# FPGA_PWR.net
KiCad netlist of a schematic drawn in Altium Designer
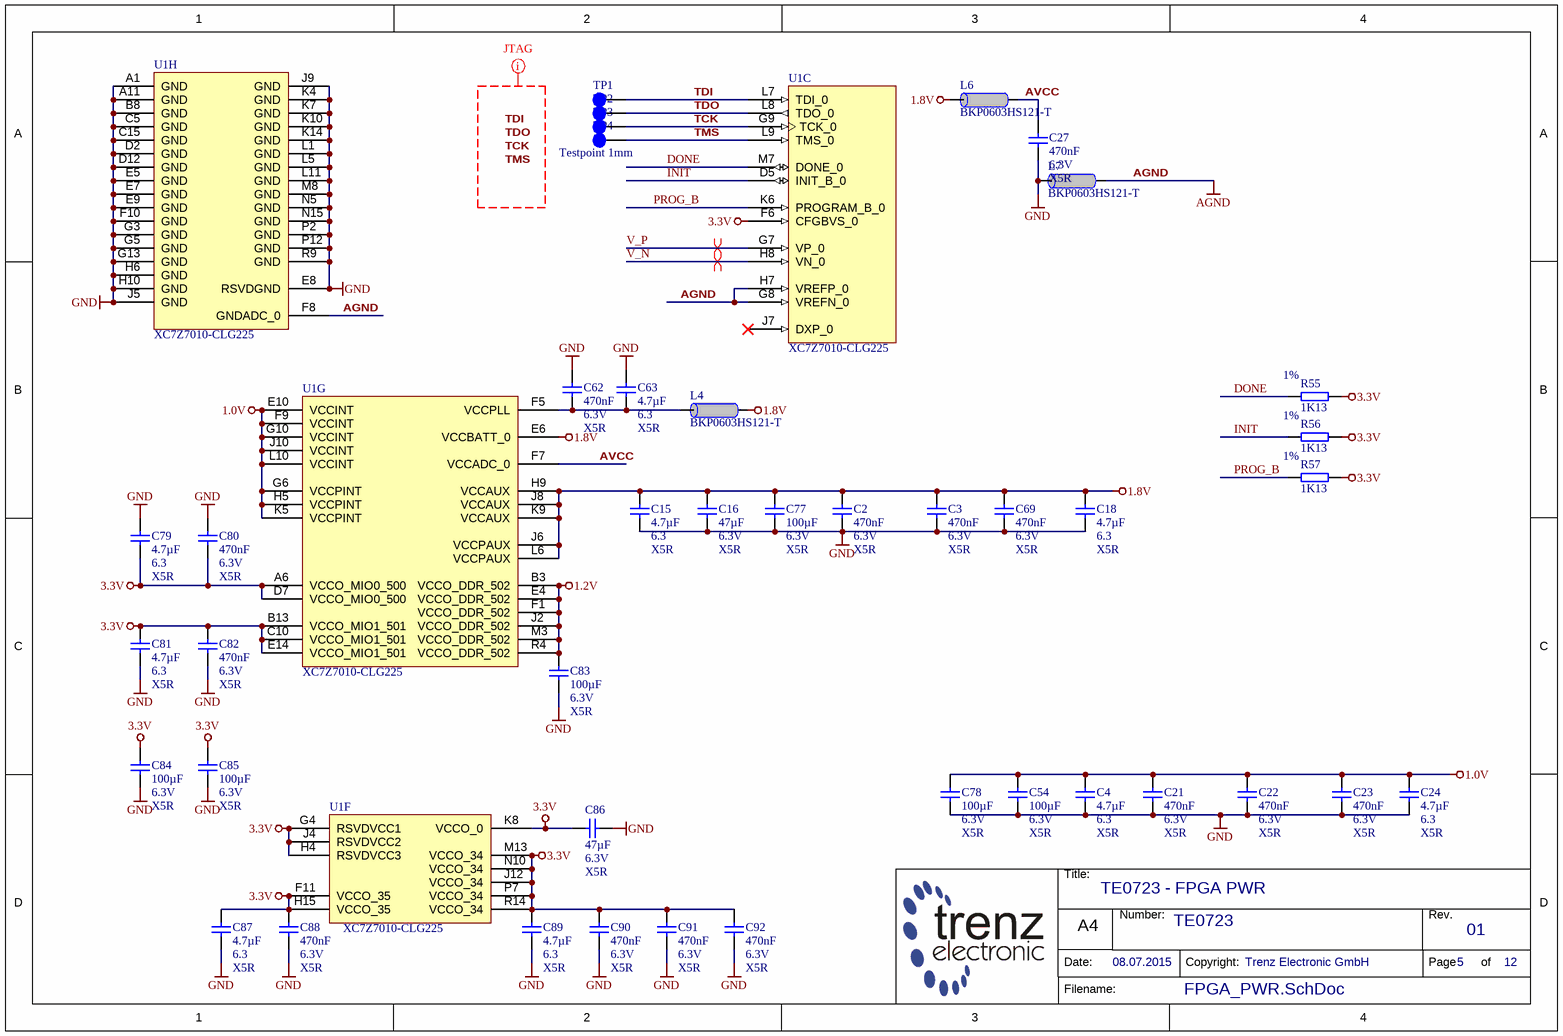
[diagram p0: FPGA_PWR.SchDoc]

(export (version "E")
  (design (tool "Eeschema 10.0.6"))
  (components
    (comp (ref "C2")
      (value "470nF")
      (footprint "CAPC0603X33N")
      (description "KON 470nF X5R 6.3V SMD 20%")
      (fields
        (field (name "VOLTAGE") "6.3V")
        (field (name "TECHNOLOGY") "X5R")
        (field (name "TOLERANCE") "20%")
      )
      (libsource (lib "TE") (part "CAP-NP"))
    )
    (comp (ref "C3")
      (value "470nF")
      (footprint "CAPC0603X33N")
      (description "KON 470nF X5R 6.3V SMD 20%")
      (fields
        (field (name "VOLTAGE") "6.3V")
        (field (name "TECHNOLOGY") "X5R")
        (field (name "TOLERANCE") "20%")
      )
      (libsource (lib "TE") (part "CAP-NP"))
    )
    (comp (ref "C4")
      (value "4.7µF")
      (footprint "CAPC1005X60N")
      (description "KON 4.7µF 6.3V X5R SMD 20%")
      (fields
        (field (name "VOLTAGE") "6.3")
        (field (name "TECHNOLOGY") "X5R")
        (field (name "TOLERANCE") "20%")
      )
      (libsource (lib "TE") (part "CAP-NP"))
    )
    (comp (ref "C15")
      (value "4.7µF")
      (footprint "CAPC1005X60N")
      (description "KON 4.7µF 6.3V X5R SMD 20%")
      (fields
        (field (name "VOLTAGE") "6.3")
        (field (name "TECHNOLOGY") "X5R")
        (field (name "TOLERANCE") "20%")
      )
      (libsource (lib "TE") (part "CAP-NP"))
    )
    (comp (ref "C16")
      (value "47µF")
      (footprint "CAPC2012X135N")
      (description "KON 47µF 6,3V  X5R SMD 20%")
      (fields
        (field (name "VOLTAGE") "6.3V")
        (field (name "TECHNOLOGY") "X5R")
        (field (name "TOLERANCE") "20%")
      )
      (libsource (lib "TE") (part "CAP-NP"))
    )
    (comp (ref "C18")
      (value "4.7µF")
      (footprint "CAPC1005X60N")
      (description "KON 4.7µF 6.3V X5R SMD 20%")
      (fields
        (field (name "VOLTAGE") "6.3")
        (field (name "TECHNOLOGY") "X5R")
        (field (name "TOLERANCE") "20%")
      )
      (libsource (lib "TE") (part "CAP-NP"))
    )
    (comp (ref "C21")
      (value "470nF")
      (footprint "CAPC0603X33N")
      (description "KON 470nF X5R 6.3V SMD 20%")
      (fields
        (field (name "VOLTAGE") "6.3V")
        (field (name "TECHNOLOGY") "X5R")
        (field (name "TOLERANCE") "20%")
      )
      (libsource (lib "TE") (part "CAP-NP"))
    )
    (comp (ref "C22")
      (value "470nF")
      (footprint "CAPC0603X33N")
      (description "KON 470nF X5R 6.3V SMD 20%")
      (fields
        (field (name "VOLTAGE") "6.3V")
        (field (name "TECHNOLOGY") "X5R")
        (field (name "TOLERANCE") "20%")
      )
      (libsource (lib "TE") (part "CAP-NP"))
    )
    (comp (ref "C23")
      (value "470nF")
      (footprint "CAPC0603X33N")
      (description "KON 470nF X5R 6.3V SMD 20%")
      (fields
        (field (name "VOLTAGE") "6.3V")
        (field (name "TECHNOLOGY") "X5R")
        (field (name "TOLERANCE") "20%")
      )
      (libsource (lib "TE") (part "CAP-NP"))
    )
    (comp (ref "C24")
      (value "4.7µF")
      (footprint "CAPC1005X60N")
      (description "KON 4.7µF 6.3V X5R SMD 20%")
      (fields
        (field (name "VOLTAGE") "6.3")
        (field (name "TECHNOLOGY") "X5R")
        (field (name "TOLERANCE") "20%")
      )
      (libsource (lib "TE") (part "CAP-NP"))
    )
    (comp (ref "C27")
      (value "470nF")
      (footprint "CAPC0603X33N")
      (description "KON 470nF X5R 6.3V SMD 20%")
      (fields
        (field (name "VOLTAGE") "6.3V")
        (field (name "TECHNOLOGY") "X5R")
        (field (name "TOLERANCE") "20%")
      )
      (libsource (lib "TE") (part "CAP-NP"))
    )
    (comp (ref "C54")
      (value "100µF")
      (footprint "CAPC3216X180N")
      (description "KON 100µF 6,3V X5R SMD 20%")
      (fields
        (field (name "VOLTAGE") "6.3V")
        (field (name "TECHNOLOGY") "X5R")
        (field (name "TOLERANCE") "20%")
      )
      (libsource (lib "TE") (part "CAP-NP"))
    )
    (comp (ref "C62")
      (value "470nF")
      (footprint "CAPC0603X33N")
      (description "KON 470nF X5R 6.3V SMD 20%")
      (fields
        (field (name "VOLTAGE") "6.3V")
        (field (name "TECHNOLOGY") "X5R")
        (field (name "TOLERANCE") "20%")
      )
      (libsource (lib "TE") (part "CAP-NP"))
    )
    (comp (ref "C63")
      (value "4.7µF")
      (footprint "CAPC1005X60N")
      (description "KON 4.7µF 6.3V X5R SMD 20%")
      (fields
        (field (name "VOLTAGE") "6.3")
        (field (name "TECHNOLOGY") "X5R")
        (field (name "TOLERANCE") "20%")
      )
      (libsource (lib "TE") (part "CAP-NP"))
    )
    (comp (ref "C69")
      (value "470nF")
      (footprint "CAPC0603X33N")
      (description "KON 470nF X5R 6.3V SMD 20%")
      (fields
        (field (name "VOLTAGE") "6.3V")
        (field (name "TECHNOLOGY") "X5R")
        (field (name "TOLERANCE") "20%")
      )
      (libsource (lib "TE") (part "CAP-NP"))
    )
    (comp (ref "C77")
      (value "100µF")
      (footprint "CAPC3216X180N")
      (description "KON 100µF 6,3V X5R SMD 20%")
      (fields
        (field (name "VOLTAGE") "6.3V")
        (field (name "TECHNOLOGY") "X5R")
        (field (name "TOLERANCE") "20%")
      )
      (libsource (lib "TE") (part "CAP-NP"))
    )
    (comp (ref "C78")
      (value "100µF")
      (footprint "CAPC3216X180N")
      (description "KON 100µF 6,3V X5R SMD 20%")
      (fields
        (field (name "VOLTAGE") "6.3V")
        (field (name "TECHNOLOGY") "X5R")
        (field (name "TOLERANCE") "20%")
      )
      (libsource (lib "TE") (part "CAP-NP"))
    )
    (comp (ref "C79")
      (value "4.7µF")
      (footprint "CAPC1005X60N")
      (description "KON 4.7µF 6.3V X5R SMD 20%")
      (fields
        (field (name "VOLTAGE") "6.3")
        (field (name "TECHNOLOGY") "X5R")
        (field (name "TOLERANCE") "20%")
      )
      (libsource (lib "TE") (part "CAP-NP"))
    )
    (comp (ref "C80")
      (value "470nF")
      (footprint "CAPC0603X33N")
      (description "KON 470nF X5R 6.3V SMD 20%")
      (fields
        (field (name "VOLTAGE") "6.3V")
        (field (name "TECHNOLOGY") "X5R")
        (field (name "TOLERANCE") "20%")
      )
      (libsource (lib "TE") (part "CAP-NP"))
    )
    (comp (ref "C81")
      (value "4.7µF")
      (footprint "CAPC1005X60N")
      (description "KON 4.7µF 6.3V X5R SMD 20%")
      (fields
        (field (name "VOLTAGE") "6.3")
        (field (name "TECHNOLOGY") "X5R")
        (field (name "TOLERANCE") "20%")
      )
      (libsource (lib "TE") (part "CAP-NP"))
    )
    (comp (ref "C82")
      (value "470nF")
      (footprint "CAPC0603X33N")
      (description "KON 470nF X5R 6.3V SMD 20%")
      (fields
        (field (name "VOLTAGE") "6.3V")
        (field (name "TECHNOLOGY") "X5R")
        (field (name "TOLERANCE") "20%")
      )
      (libsource (lib "TE") (part "CAP-NP"))
    )
    (comp (ref "C83")
      (value "100µF")
      (footprint "CAPC3216X180N")
      (description "KON 100µF 6,3V X5R SMD 20%")
      (fields
        (field (name "VOLTAGE") "6.3V")
        (field (name "TECHNOLOGY") "X5R")
        (field (name "TOLERANCE") "20%")
      )
      (libsource (lib "TE") (part "CAP-NP"))
    )
    (comp (ref "C84")
      (value "100µF")
      (footprint "CAPC3216X180N")
      (description "KON 100µF 6,3V X5R SMD 20%")
      (fields
        (field (name "VOLTAGE") "6.3V")
        (field (name "TECHNOLOGY") "X5R")
        (field (name "TOLERANCE") "20%")
      )
      (libsource (lib "TE") (part "CAP-NP"))
    )
    (comp (ref "C85")
      (value "100µF")
      (footprint "CAPC3216X180N")
      (description "KON 100µF 6,3V X5R SMD 20%")
      (fields
        (field (name "VOLTAGE") "6.3V")
        (field (name "TECHNOLOGY") "X5R")
        (field (name "TOLERANCE") "20%")
      )
      (libsource (lib "TE") (part "CAP-NP"))
    )
    (comp (ref "C86")
      (value "47µF")
      (footprint "CAPC2012X135N")
      (description "KON 47µF 6,3V  X5R SMD 20%")
      (fields
        (field (name "VOLTAGE") "6.3V")
        (field (name "TECHNOLOGY") "X5R")
        (field (name "TOLERANCE") "20%")
      )
      (libsource (lib "TE") (part "CAP-NP"))
    )
    (comp (ref "C87")
      (value "4.7µF")
      (footprint "CAPC1005X60N")
      (description "KON 4.7µF 6.3V X5R SMD 20%")
      (fields
        (field (name "VOLTAGE") "6.3")
        (field (name "TECHNOLOGY") "X5R")
        (field (name "TOLERANCE") "20%")
      )
      (libsource (lib "TE") (part "CAP-NP"))
    )
    (comp (ref "C88")
      (value "470nF")
      (footprint "CAPC0603X33N")
      (description "KON 470nF X5R 6.3V SMD 20%")
      (fields
        (field (name "VOLTAGE") "6.3V")
        (field (name "TECHNOLOGY") "X5R")
        (field (name "TOLERANCE") "20%")
      )
      (libsource (lib "TE") (part "CAP-NP"))
    )
    (comp (ref "C89")
      (value "4.7µF")
      (footprint "CAPC1005X60N")
      (description "KON 4.7µF 6.3V X5R SMD 20%")
      (fields
        (field (name "VOLTAGE") "6.3")
        (field (name "TECHNOLOGY") "X5R")
        (field (name "TOLERANCE") "20%")
      )
      (libsource (lib "TE") (part "CAP-NP"))
    )
    (comp (ref "C90")
      (value "470nF")
      (footprint "CAPC0603X33N")
      (description "KON 470nF X5R 6.3V SMD 20%")
      (fields
        (field (name "VOLTAGE") "6.3V")
        (field (name "TECHNOLOGY") "X5R")
        (field (name "TOLERANCE") "20%")
      )
      (libsource (lib "TE") (part "CAP-NP"))
    )
    (comp (ref "C91")
      (value "470nF")
      (footprint "CAPC0603X33N")
      (description "KON 470nF X5R 6.3V SMD 20%")
      (fields
        (field (name "VOLTAGE") "6.3V")
        (field (name "TECHNOLOGY") "X5R")
        (field (name "TOLERANCE") "20%")
      )
      (libsource (lib "TE") (part "CAP-NP"))
    )
    (comp (ref "C92")
      (value "470nF")
      (footprint "CAPC0603X33N")
      (description "KON 470nF X5R 6.3V SMD 20%")
      (fields
        (field (name "VOLTAGE") "6.3V")
        (field (name "TECHNOLOGY") "X5R")
        (field (name "TOLERANCE") "20%")
      )
      (libsource (lib "TE") (part "CAP-NP"))
    )
    (comp (ref "L4")
      (value "BKP0603HS121-T")
      (footprint "INDC0603X33N")
      (description "Ferritdurchführung SMD 0201")
      (fields (field (name "TOLERANCE") "25%"))
      (libsource (lib "TE") (part "Ferritperle"))
    )
    (comp (ref "L6")
      (value "BKP0603HS121-T")
      (footprint "INDC0603X33N")
      (description "Ferritdurchführung SMD 0201")
      (fields (field (name "TOLERANCE") "25%"))
      (libsource (lib "TE") (part "Ferritperle"))
    )
    (comp (ref "L7")
      (value "BKP0603HS121-T")
      (footprint "INDC0603X33N")
      (description "Ferritdurchführung SMD 0201")
      (fields (field (name "TOLERANCE") "25%"))
      (libsource (lib "TE") (part "Ferritperle"))
    )
    (comp (ref "R55")
      (value "1K13")
      (footprint "RESC1005X40N")
      (description "WID SMD 1K13 1% 0,063W")
      (fields (field (name "TOLERANCE") "1%"))
      (libsource (lib "TE") (part "RES"))
    )
    (comp (ref "R56")
      (value "1K13")
      (footprint "RESC1005X40N")
      (description "WID SMD 1K13 1% 0,063W")
      (fields (field (name "TOLERANCE") "1%"))
      (libsource (lib "TE") (part "RES"))
    )
    (comp (ref "R57")
      (value "1K13")
      (footprint "RESC1005X40N")
      (description "WID SMD 1K13 1% 0,063W")
      (fields (field (name "TOLERANCE") "1%"))
      (libsource (lib "TE") (part "RES"))
    )
    (comp (ref "TP1") (value "Testpoint 1mm") (footprint "TP_1mm") (libsource (lib "TE") (part "TP")))
    (comp (ref "TP2") (value "Testpoint 1mm") (footprint "TP_1mm") (libsource (lib "TE") (part "TP")))
    (comp (ref "TP3") (value "Testpoint 1mm") (footprint "TP_1mm") (libsource (lib "TE") (part "TP")))
    (comp (ref "TP4") (value "Testpoint 1mm") (footprint "TP_1mm") (libsource (lib "TE") (part "TP")))
    (comp (ref "U1") (value "XC7Z7010-CLG225") (libsource (lib "XC7Z010-CLG225") (part "XC7Z7010-CLG225")))
  )
  (nets
    (net (code "1") (name "/AVCC") (class "Default")
      (node (ref "C27") (pin "2") (pinfunction "2_2") (pintype "passive"))
      (node (ref "L6") (pin "1") (pinfunction "1_1") (pintype "passive"))
      (node (ref "U1") (pin "F7") (pinfunction "VCCADC_0_F7") (pintype "power_in"))
    )
    (net (code "2") (name "/DONE") (class "Default")
      (node (ref "R55") (pin "1") (pinfunction "1_1") (pintype "passive"))
      (node (ref "U1") (pin "M7") (pinfunction "DONE_0_M7") (pintype "bidirectional"))
    )
    (net (code "3") (name "/INIT") (class "Default")
      (node (ref "R56") (pin "1") (pinfunction "1_1") (pintype "passive"))
      (node (ref "U1") (pin "D5") (pinfunction "INIT_B_0_D5") (pintype "bidirectional"))
    )
    (net (code "4") (name "/PROG_B") (class "Default")
      (node (ref "R57") (pin "1") (pinfunction "1_1") (pintype "passive"))
      (node (ref "U1") (pin "K6") (pinfunction "PROGRAM_B_0_K6") (pintype "input"))
    )
    (net (code "5") (name "/TCK") (class "Default")
      (node (ref "TP3") (pin "1") (pintype "passive"))
      (node (ref "U1") (pin "G9") (pinfunction "TCK_0_G9") (pintype "input"))
    )
    (net (code "6") (name "/TDI") (class "Default")
      (node (ref "TP1") (pin "1") (pintype "passive"))
      (node (ref "U1") (pin "L7") (pinfunction "TDI_0_L7") (pintype "input"))
    )
    (net (code "7") (name "/TDO") (class "Default")
      (node (ref "TP2") (pin "1") (pintype "passive"))
      (node (ref "U1") (pin "L8") (pinfunction "TDO_0_L8") (pintype "output"))
    )
    (net (code "8") (name "/TMS") (class "Default")
      (node (ref "TP4") (pin "1") (pintype "passive"))
      (node (ref "U1") (pin "L9") (pinfunction "TMS_0_L9") (pintype "input"))
    )
    (net (code "9") (name "/V_N") (class "Default")
      (node (ref "U1") (pin "H8") (pinfunction "VN_0_H8") (pintype "input"))
    )
    (net (code "10") (name "/V_P") (class "Default")
      (node (ref "U1") (pin "G7") (pinfunction "VP_0_G7") (pintype "input"))
    )
    (net (code "11") (name "1.0V") (class "Default")
      (node (ref "C21") (pin "2") (pinfunction "2_2") (pintype "passive"))
      (node (ref "C22") (pin "2") (pinfunction "2_2") (pintype "passive"))
      (node (ref "C23") (pin "2") (pinfunction "2_2") (pintype "passive"))
      (node (ref "C24") (pin "1") (pinfunction "1_1") (pintype "passive"))
      (node (ref "C4") (pin "1") (pinfunction "1_1") (pintype "passive"))
      (node (ref "C54") (pin "1") (pinfunction "1_1") (pintype "passive"))
      (node (ref "C78") (pin "1") (pinfunction "1_1") (pintype "passive"))
      (node (ref "U1") (pin "E10") (pinfunction "VCCINT_E10") (pintype "power_in"))
      (node (ref "U1") (pin "F9") (pinfunction "VCCINT_F9") (pintype "power_in"))
      (node (ref "U1") (pin "G10") (pinfunction "VCCINT_G10") (pintype "power_in"))
      (node (ref "U1") (pin "G6") (pinfunction "VCCPINT_G6") (pintype "power_in"))
      (node (ref "U1") (pin "H5") (pinfunction "VCCPINT_H5") (pintype "power_in"))
      (node (ref "U1") (pin "J10") (pinfunction "VCCINT_J10") (pintype "power_in"))
      (node (ref "U1") (pin "K5") (pinfunction "VCCPINT_K5") (pintype "power_in"))
      (node (ref "U1") (pin "L10") (pinfunction "VCCINT_L10") (pintype "power_in"))
    )
    (net (code "12") (name "1.2V") (class "Default")
      (node (ref "C83") (pin "1") (pinfunction "1_1") (pintype "passive"))
      (node (ref "U1") (pin "B3") (pinfunction "VCCO_DDR_502_B3") (pintype "power_in"))
      (node (ref "U1") (pin "E4") (pinfunction "VCCO_DDR_502_E4") (pintype "power_in"))
      (node (ref "U1") (pin "F1") (pinfunction "VCCO_DDR_502_F1") (pintype "power_in"))
      (node (ref "U1") (pin "J2") (pinfunction "VCCO_DDR_502_J2") (pintype "power_in"))
      (node (ref "U1") (pin "M3") (pinfunction "VCCO_DDR_502_M3") (pintype "power_in"))
      (node (ref "U1") (pin "R4") (pinfunction "VCCO_DDR_502_R4") (pintype "power_in"))
    )
    (net (code "13") (name "1.8V") (class "Default")
      (node (ref "C15") (pin "1") (pinfunction "1_1") (pintype "passive"))
      (node (ref "C16") (pin "1") (pinfunction "1_1") (pintype "passive"))
      (node (ref "C18") (pin "1") (pinfunction "1_1") (pintype "passive"))
      (node (ref "C2") (pin "2") (pinfunction "2_2") (pintype "passive"))
      (node (ref "C3") (pin "1") (pinfunction "1_1") (pintype "passive"))
      (node (ref "C69") (pin "1") (pinfunction "1_1") (pintype "passive"))
      (node (ref "C77") (pin "1") (pinfunction "1_1") (pintype "passive"))
      (node (ref "L4") (pin "1") (pinfunction "1_1") (pintype "passive"))
      (node (ref "L6") (pin "2") (pinfunction "2_2") (pintype "passive"))
      (node (ref "U1") (pin "E6") (pinfunction "VCCBATT_0_E6") (pintype "power_in"))
      (node (ref "U1") (pin "H9") (pinfunction "VCCAUX_H9") (pintype "power_in"))
      (node (ref "U1") (pin "J6") (pinfunction "VCCPAUX_J6") (pintype "power_in"))
      (node (ref "U1") (pin "J8") (pinfunction "VCCAUX_J8") (pintype "power_in"))
      (node (ref "U1") (pin "K9") (pinfunction "VCCAUX_K9") (pintype "power_in"))
      (node (ref "U1") (pin "L6") (pinfunction "VCCPAUX_L6") (pintype "power_in"))
    )
    (net (code "14") (name "3.3V") (class "Default")
      (node (ref "C79") (pin "1") (pinfunction "1_1") (pintype "passive"))
      (node (ref "C80") (pin "2") (pinfunction "2_2") (pintype "passive"))
      (node (ref "C81") (pin "1") (pinfunction "1_1") (pintype "passive"))
      (node (ref "C82") (pin "2") (pinfunction "2_2") (pintype "passive"))
      (node (ref "C84") (pin "1") (pinfunction "1_1") (pintype "passive"))
      (node (ref "C85") (pin "1") (pinfunction "1_1") (pintype "passive"))
      (node (ref "C86") (pin "2") (pinfunction "2_2") (pintype "passive"))
      (node (ref "C87") (pin "1") (pinfunction "1_1") (pintype "passive"))
      (node (ref "C88") (pin "2") (pinfunction "2_2") (pintype "passive"))
      (node (ref "C89") (pin "1") (pinfunction "1_1") (pintype "passive"))
      (node (ref "C90") (pin "2") (pinfunction "2_2") (pintype "passive"))
      (node (ref "C91") (pin "2") (pinfunction "2_2") (pintype "passive"))
      (node (ref "C92") (pin "2") (pinfunction "2_2") (pintype "passive"))
      (node (ref "R55") (pin "2") (pinfunction "2_2") (pintype "passive"))
      (node (ref "R56") (pin "2") (pinfunction "2_2") (pintype "passive"))
      (node (ref "R57") (pin "2") (pinfunction "2_2") (pintype "passive"))
      (node (ref "U1") (pin "A6") (pinfunction "VCCO_MIO0_500_A6") (pintype "power_in"))
      (node (ref "U1") (pin "B13") (pinfunction "VCCO_MIO1_501_B13") (pintype "power_in"))
      (node (ref "U1") (pin "C10") (pinfunction "VCCO_MIO1_501_C10") (pintype "power_in"))
      (node (ref "U1") (pin "D7") (pinfunction "VCCO_MIO0_500_D7") (pintype "power_in"))
      (node (ref "U1") (pin "E14") (pinfunction "VCCO_MIO1_501_E14") (pintype "power_in"))
      (node (ref "U1") (pin "F11") (pinfunction "VCCO_35_F11") (pintype "power_in"))
      (node (ref "U1") (pin "F6") (pinfunction "CFGBVS_0_F6") (pintype "input"))
      (node (ref "U1") (pin "G4") (pinfunction "RSVDVCC1_G4") (pintype "power_in"))
      (node (ref "U1") (pin "H15") (pinfunction "VCCO_35_H15") (pintype "power_in"))
      (node (ref "U1") (pin "H4") (pinfunction "RSVDVCC3_H4") (pintype "power_in"))
      (node (ref "U1") (pin "J12") (pinfunction "VCCO_34_J12") (pintype "power_in"))
      (node (ref "U1") (pin "J4") (pinfunction "RSVDVCC2_J4") (pintype "power_in"))
      (node (ref "U1") (pin "K8") (pinfunction "VCCO_0_K8") (pintype "power_in"))
      (node (ref "U1") (pin "M13") (pinfunction "VCCO_34_M13") (pintype "power_in"))
      (node (ref "U1") (pin "N10") (pinfunction "VCCO_34_N10") (pintype "power_in"))
      (node (ref "U1") (pin "P7") (pinfunction "VCCO_34_P7") (pintype "power_in"))
      (node (ref "U1") (pin "R14") (pinfunction "VCCO_34_R14") (pintype "power_in"))
    )
    (net (code "15") (name "AGND") (class "Default")
      (node (ref "L7") (pin "1") (pinfunction "1_1") (pintype "passive"))
      (node (ref "U1") (pin "F8") (pinfunction "GNDADC_0_F8") (pintype "power_in"))
      (node (ref "U1") (pin "G8") (pinfunction "VREFN_0_G8") (pintype "input"))
      (node (ref "U1") (pin "H7") (pinfunction "VREFP_0_H7") (pintype "input"))
    )
    (net (code "16") (name "GND") (class "Default")
      (node (ref "C15") (pin "2") (pinfunction "2_2") (pintype "passive"))
      (node (ref "C16") (pin "2") (pinfunction "2_2") (pintype "passive"))
      (node (ref "C18") (pin "2") (pinfunction "2_2") (pintype "passive"))
      (node (ref "C2") (pin "1") (pinfunction "1_1") (pintype "passive"))
      (node (ref "C21") (pin "1") (pinfunction "1_1") (pintype "passive"))
      (node (ref "C22") (pin "1") (pinfunction "1_1") (pintype "passive"))
      (node (ref "C23") (pin "1") (pinfunction "1_1") (pintype "passive"))
      (node (ref "C24") (pin "2") (pinfunction "2_2") (pintype "passive"))
      (node (ref "C27") (pin "1") (pinfunction "1_1") (pintype "passive"))
      (node (ref "C3") (pin "2") (pinfunction "2_2") (pintype "passive"))
      (node (ref "C4") (pin "2") (pinfunction "2_2") (pintype "passive"))
      (node (ref "C54") (pin "2") (pinfunction "2_2") (pintype "passive"))
      (node (ref "C62") (pin "1") (pinfunction "1_1") (pintype "passive"))
      (node (ref "C63") (pin "1") (pinfunction "1_1") (pintype "passive"))
      (node (ref "C69") (pin "2") (pinfunction "2_2") (pintype "passive"))
      (node (ref "C77") (pin "2") (pinfunction "2_2") (pintype "passive"))
      (node (ref "C78") (pin "2") (pinfunction "2_2") (pintype "passive"))
      (node (ref "C79") (pin "2") (pinfunction "2_2") (pintype "passive"))
      (node (ref "C80") (pin "1") (pinfunction "1_1") (pintype "passive"))
      (node (ref "C81") (pin "2") (pinfunction "2_2") (pintype "passive"))
      (node (ref "C82") (pin "1") (pinfunction "1_1") (pintype "passive"))
      (node (ref "C83") (pin "2") (pinfunction "2_2") (pintype "passive"))
      (node (ref "C84") (pin "2") (pinfunction "2_2") (pintype "passive"))
      (node (ref "C85") (pin "2") (pinfunction "2_2") (pintype "passive"))
      (node (ref "C86") (pin "1") (pinfunction "1_1") (pintype "passive"))
      (node (ref "C87") (pin "2") (pinfunction "2_2") (pintype "passive"))
      (node (ref "C88") (pin "1") (pinfunction "1_1") (pintype "passive"))
      (node (ref "C89") (pin "2") (pinfunction "2_2") (pintype "passive"))
      (node (ref "C90") (pin "1") (pinfunction "1_1") (pintype "passive"))
      (node (ref "C91") (pin "1") (pinfunction "1_1") (pintype "passive"))
      (node (ref "C92") (pin "1") (pinfunction "1_1") (pintype "passive"))
      (node (ref "L7") (pin "2") (pinfunction "2_2") (pintype "passive"))
      (node (ref "U1") (pin "A1") (pinfunction "GND_A1") (pintype "power_in"))
      (node (ref "U1") (pin "A11") (pinfunction "GND_A11") (pintype "power_in"))
      (node (ref "U1") (pin "B8") (pinfunction "GND_B8") (pintype "power_in"))
      (node (ref "U1") (pin "C15") (pinfunction "GND_C15") (pintype "power_in"))
      (node (ref "U1") (pin "C5") (pinfunction "GND_C5") (pintype "power_in"))
      (node (ref "U1") (pin "D12") (pinfunction "GND_D12") (pintype "power_in"))
      (node (ref "U1") (pin "D2") (pinfunction "GND_D2") (pintype "power_in"))
      (node (ref "U1") (pin "E5") (pinfunction "GND_E5") (pintype "power_in"))
      (node (ref "U1") (pin "E7") (pinfunction "GND_E7") (pintype "power_in"))
      (node (ref "U1") (pin "E8") (pinfunction "RSVDGND_E8") (pintype "power_in"))
      (node (ref "U1") (pin "E9") (pinfunction "GND_E9") (pintype "power_in"))
      (node (ref "U1") (pin "F10") (pinfunction "GND_F10") (pintype "power_in"))
      (node (ref "U1") (pin "G13") (pinfunction "GND_G13") (pintype "power_in"))
      (node (ref "U1") (pin "G3") (pinfunction "GND_G3") (pintype "power_in"))
      (node (ref "U1") (pin "G5") (pinfunction "GND_G5") (pintype "power_in"))
      (node (ref "U1") (pin "H10") (pinfunction "GND_H10") (pintype "power_in"))
      (node (ref "U1") (pin "H6") (pinfunction "GND_H6") (pintype "power_in"))
      (node (ref "U1") (pin "J5") (pinfunction "GND_J5") (pintype "power_in"))
      (node (ref "U1") (pin "J9") (pinfunction "GND_J9") (pintype "power_in"))
      (node (ref "U1") (pin "K10") (pinfunction "GND_K10") (pintype "power_in"))
      (node (ref "U1") (pin "K14") (pinfunction "GND_K14") (pintype "power_in"))
      (node (ref "U1") (pin "K4") (pinfunction "GND_K4") (pintype "power_in"))
      (node (ref "U1") (pin "K7") (pinfunction "GND_K7") (pintype "power_in"))
      (node (ref "U1") (pin "L1") (pinfunction "GND_L1") (pintype "power_in"))
      (node (ref "U1") (pin "L11") (pinfunction "GND_L11") (pintype "power_in"))
      (node (ref "U1") (pin "L5") (pinfunction "GND_L5") (pintype "power_in"))
      (node (ref "U1") (pin "M8") (pinfunction "GND_M8") (pintype "power_in"))
      (node (ref "U1") (pin "N15") (pinfunction "GND_N15") (pintype "power_in"))
      (node (ref "U1") (pin "N5") (pinfunction "GND_N5") (pintype "power_in"))
      (node (ref "U1") (pin "P12") (pinfunction "GND_P12") (pintype "power_in"))
      (node (ref "U1") (pin "P2") (pinfunction "GND_P2") (pintype "power_in"))
      (node (ref "U1") (pin "R9") (pinfunction "GND_R9") (pintype "power_in"))
    )
    (net (code "17") (name "Net-(U1G-VCCPLL)") (class "Default")
      (node (ref "C62") (pin "2") (pinfunction "2_2") (pintype "passive"))
      (node (ref "C63") (pin "2") (pinfunction "2_2") (pintype "passive"))
      (node (ref "L4") (pin "2") (pinfunction "2_2") (pintype "passive"))
      (node (ref "U1") (pin "F5") (pinfunction "VCCPLL_F5") (pintype "power_in"))
    )
    (net (code "18") (name "unconnected-(U1C-DXP_0-PadJ7)") (class "Default")
      (node (ref "U1") (pin "J7") (pinfunction "DXP_0_J7") (pintype "input+no_connect"))
    )
  )
)
